# Sheet1.net
KiCad netlist of a schematic drawn in Altium Designer
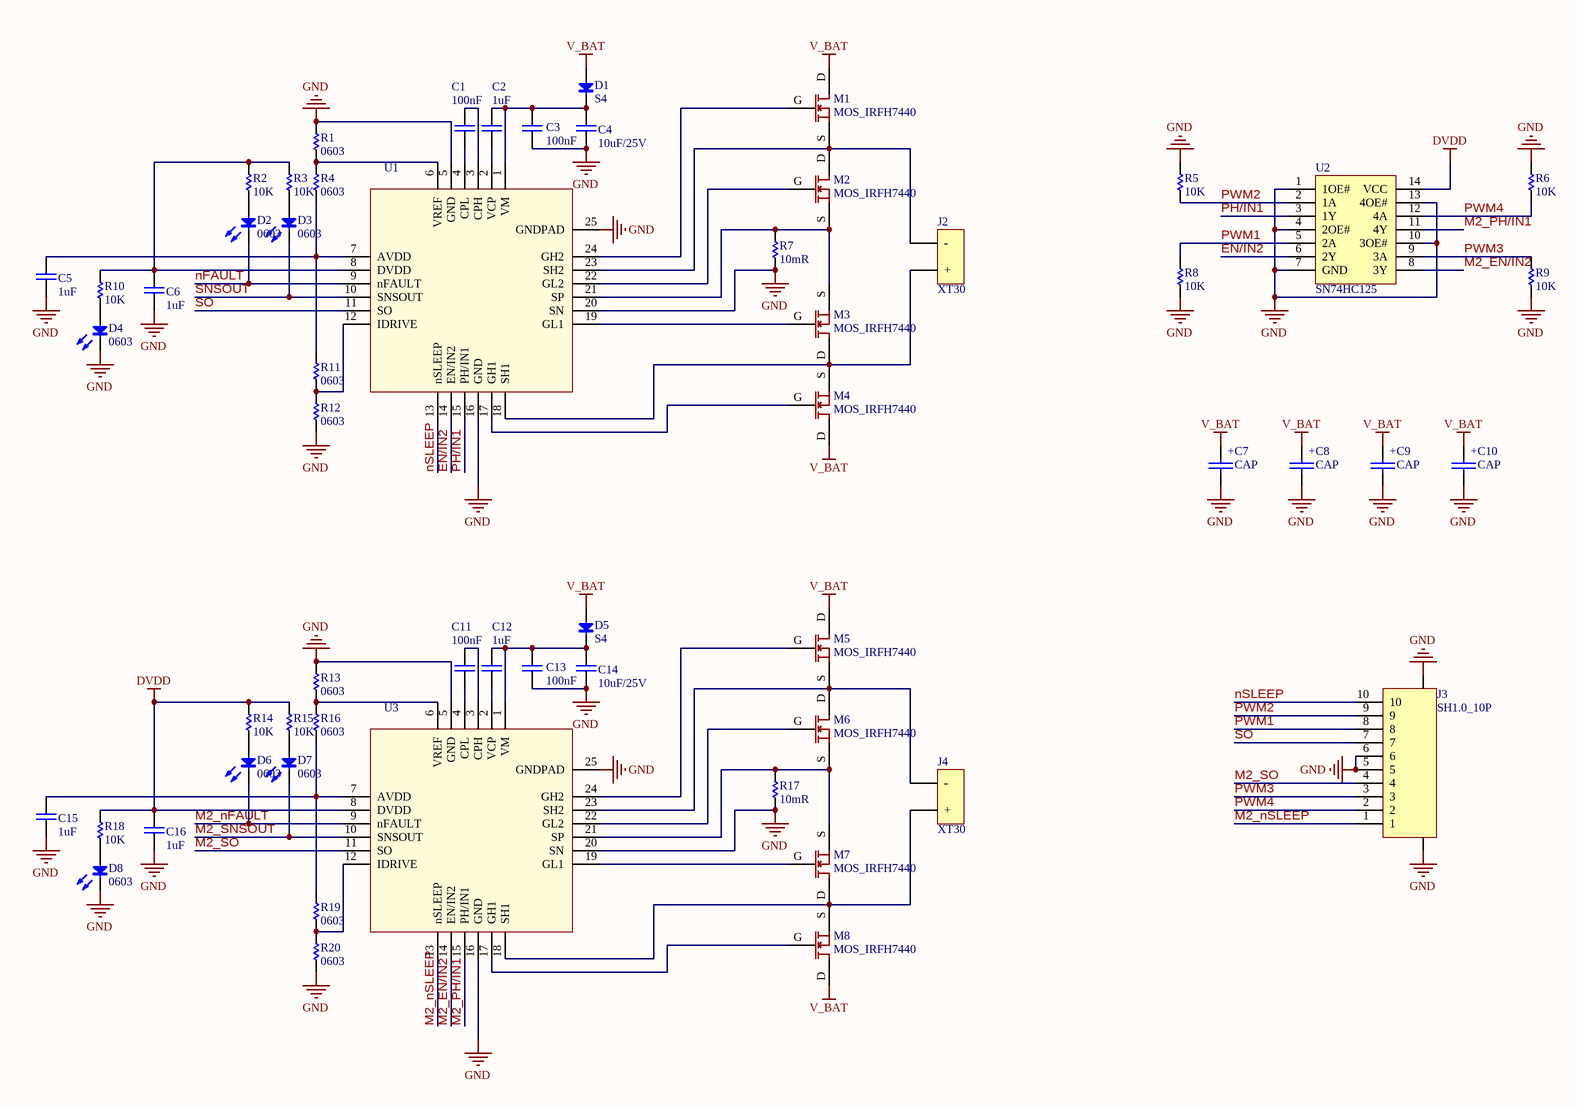
[diagram p0: Sheet1.SchDoc]

(export (version "E")
  (design (tool "Eeschema 10.0.6"))
  (components
    (comp (ref "C1") (value "100nF") (footprint "0603C") (libsource (lib "CPH_LIB") (part "0603-C")))
    (comp (ref "C2") (value "1uF") (footprint "0603C") (libsource (lib "CPH_LIB") (part "0603-C")))
    (comp (ref "C3") (value "100nF") (footprint "0603C") (libsource (lib "CPH_LIB") (part "0603-C")))
    (comp (ref "C4") (value "10uF/25V") (footprint "0805C") (libsource (lib "CPH_LIB") (part "0805-C")))
    (comp (ref "C5") (value "1uF") (footprint "0603C") (libsource (lib "CPH_LIB") (part "0603-C")))
    (comp (ref "C6") (value "1uF") (footprint "0603C") (libsource (lib "CPH_LIB") (part "0603-C")))
    (comp (ref "C7")
      (value "CAP")
      (footprint "CAP-8*11.5")
      (description "插件电解电容")
      (libsource (lib "CPH_LIB") (part "CAP"))
    )
    (comp (ref "C8")
      (value "CAP")
      (footprint "CAP-8*11.5")
      (description "插件电解电容")
      (libsource (lib "CPH_LIB") (part "CAP"))
    )
    (comp (ref "C9")
      (value "CAP")
      (footprint "CAP-8*11.5")
      (description "插件电解电容")
      (libsource (lib "CPH_LIB") (part "CAP"))
    )
    (comp (ref "C10")
      (value "CAP")
      (footprint "CAP-8*11.5")
      (description "插件电解电容")
      (libsource (lib "CPH_LIB") (part "CAP"))
    )
    (comp (ref "C11") (value "100nF") (footprint "0603C") (libsource (lib "CPH_LIB") (part "0603-C")))
    (comp (ref "C12") (value "1uF") (footprint "0603C") (libsource (lib "CPH_LIB") (part "0603-C")))
    (comp (ref "C13") (value "100nF") (footprint "0603C") (libsource (lib "CPH_LIB") (part "0603-C")))
    (comp (ref "C14") (value "10uF/25V") (footprint "0805C") (libsource (lib "CPH_LIB") (part "0805-C")))
    (comp (ref "C15") (value "1uF") (footprint "0603C") (libsource (lib "CPH_LIB") (part "0603-C")))
    (comp (ref "C16") (value "1uF") (footprint "0603C") (libsource (lib "CPH_LIB") (part "0603-C")))
    (comp (ref "D1")
      (value "S4")
      (footprint "SOD-123")
      (description "二极管")
      (libsource (lib "CPH_LIB") (part "DIODE-SOD123"))
    )
    (comp (ref "D2")
      (value "0603")
      (footprint "0603-LED")
      (fields (field (name "DESIGNER") "www.dratk.com"))
      (libsource (lib "CPH_LIB") (part "0603-LED"))
    )
    (comp (ref "D3")
      (value "0603")
      (footprint "0603-LED")
      (fields (field (name "DESIGNER") "www.dratk.com"))
      (libsource (lib "CPH_LIB") (part "0603-LED"))
    )
    (comp (ref "D4")
      (value "0603")
      (footprint "0603-LED")
      (fields (field (name "DESIGNER") "www.dratk.com"))
      (libsource (lib "CPH_LIB") (part "0603-LED"))
    )
    (comp (ref "D5")
      (value "S4")
      (footprint "SOD-123")
      (description "二极管")
      (libsource (lib "CPH_LIB") (part "DIODE-SOD123"))
    )
    (comp (ref "D6")
      (value "0603")
      (footprint "0603-LED")
      (fields (field (name "DESIGNER") "www.dratk.com"))
      (libsource (lib "CPH_LIB") (part "0603-LED"))
    )
    (comp (ref "D7")
      (value "0603")
      (footprint "0603-LED")
      (fields (field (name "DESIGNER") "www.dratk.com"))
      (libsource (lib "CPH_LIB") (part "0603-LED"))
    )
    (comp (ref "D8")
      (value "0603")
      (footprint "0603-LED")
      (fields (field (name "DESIGNER") "www.dratk.com"))
      (libsource (lib "CPH_LIB") (part "0603-LED"))
    )
    (comp (ref "J2")
      (value "XT30")
      (footprint "AMASS_XT30_M")
      (description "XT30_M")
      (libsource (lib "CPH_LIB") (part "AMASS_XT30_M"))
    )
    (comp (ref "J3")
      (value "SH1.0_10P")
      (footprint "SH1.0_10P")
      (libsource (lib "CPH_LIB") (part "SH1.0_10P"))
    )
    (comp (ref "J4")
      (value "XT30")
      (footprint "AMASS_XT30_M")
      (description "XT30_M")
      (libsource (lib "CPH_LIB") (part "AMASS_XT30_M"))
    )
    (comp (ref "M1")
      (value "MOS_IRFH7440")
      (footprint "MOS_IRFH7440")
      (description "NMOS")
      (libsource (lib "CPH_LIB") (part "MOS_IRFH7440"))
    )
    (comp (ref "M2")
      (value "MOS_IRFH7440")
      (footprint "MOS_IRFH7440")
      (description "NMOS")
      (libsource (lib "CPH_LIB") (part "MOS_IRFH7440"))
    )
    (comp (ref "M3")
      (value "MOS_IRFH7440")
      (footprint "MOS_IRFH7440")
      (description "NMOS")
      (libsource (lib "CPH_LIB") (part "MOS_IRFH7440"))
    )
    (comp (ref "M4")
      (value "MOS_IRFH7440")
      (footprint "MOS_IRFH7440")
      (description "NMOS")
      (libsource (lib "CPH_LIB") (part "MOS_IRFH7440"))
    )
    (comp (ref "M5")
      (value "MOS_IRFH7440")
      (footprint "MOS_IRFH7440")
      (description "NMOS")
      (libsource (lib "CPH_LIB") (part "MOS_IRFH7440"))
    )
    (comp (ref "M6")
      (value "MOS_IRFH7440")
      (footprint "MOS_IRFH7440")
      (description "NMOS")
      (libsource (lib "CPH_LIB") (part "MOS_IRFH7440"))
    )
    (comp (ref "M7")
      (value "MOS_IRFH7440")
      (footprint "MOS_IRFH7440")
      (description "NMOS")
      (libsource (lib "CPH_LIB") (part "MOS_IRFH7440"))
    )
    (comp (ref "M8")
      (value "MOS_IRFH7440")
      (footprint "MOS_IRFH7440")
      (description "NMOS")
      (libsource (lib "CPH_LIB") (part "MOS_IRFH7440"))
    )
    (comp (ref "R1") (value "0603") (footprint "0603R") (libsource (lib "CPH_LIB") (part "0603-R")))
    (comp (ref "R2") (value "10K") (footprint "0603R") (libsource (lib "CPH_LIB") (part "0603-R")))
    (comp (ref "R3") (value "10K") (footprint "0603R") (libsource (lib "CPH_LIB") (part "0603-R")))
    (comp (ref "R4") (value "0603") (footprint "0603R") (libsource (lib "CPH_LIB") (part "0603-R")))
    (comp (ref "R5") (value "10K") (footprint "0603R") (libsource (lib "CPH_LIB") (part "0603-R")))
    (comp (ref "R6") (value "10K") (footprint "0603R") (libsource (lib "CPH_LIB") (part "0603-R")))
    (comp (ref "R7") (value "10mR") (footprint "2512R") (libsource (lib "CPH_LIB") (part "2512-R")))
    (comp (ref "R8") (value "10K") (footprint "0603R") (libsource (lib "CPH_LIB") (part "0603-R")))
    (comp (ref "R9") (value "10K") (footprint "0603R") (libsource (lib "CPH_LIB") (part "0603-R")))
    (comp (ref "R10") (value "10K") (footprint "0603R") (libsource (lib "CPH_LIB") (part "0603-R")))
    (comp (ref "R11") (value "0603") (footprint "0603R") (libsource (lib "CPH_LIB") (part "0603-R")))
    (comp (ref "R12") (value "0603") (footprint "0603R") (libsource (lib "CPH_LIB") (part "0603-R")))
    (comp (ref "R13") (value "0603") (footprint "0603R") (libsource (lib "CPH_LIB") (part "0603-R")))
    (comp (ref "R14") (value "10K") (footprint "0603R") (libsource (lib "CPH_LIB") (part "0603-R")))
    (comp (ref "R15") (value "10K") (footprint "0603R") (libsource (lib "CPH_LIB") (part "0603-R")))
    (comp (ref "R16") (value "0603") (footprint "0603R") (libsource (lib "CPH_LIB") (part "0603-R")))
    (comp (ref "R17") (value "10mR") (footprint "2512R") (libsource (lib "CPH_LIB") (part "2512-R")))
    (comp (ref "R18") (value "10K") (footprint "0603R") (libsource (lib "CPH_LIB") (part "0603-R")))
    (comp (ref "R19") (value "0603") (footprint "0603R") (libsource (lib "CPH_LIB") (part "0603-R")))
    (comp (ref "R20") (value "0603") (footprint "0603R") (libsource (lib "CPH_LIB") (part "0603-R")))
    (comp (ref "U1") (value "DRV8701") (footprint "DRV8701") (libsource (lib "CPH_LIB") (part "DRV8701")))
    (comp (ref "U2")
      (value "SN74HC125")
      (footprint "TSSOP-14_L5.0-W4.4-P0.65-LS6.5-BL")
      (description "TI, 2-6V")
      (libsource (lib "CPH_LIB") (part "SN74HC125"))
    )
    (comp (ref "U3") (value "DRV8701") (footprint "DRV8701") (libsource (lib "CPH_LIB") (part "DRV8701")))
  )
  (nets
    (net (code "1") (name "/EN{slash}IN2") (class "Default")
      (node (ref "U1") (pin "14") (pinfunction "EN/IN2_14") (pintype "passive"))
      (node (ref "U2") (pin "6") (pinfunction "2Y_6") (pintype "passive"))
    )
    (net (code "2") (name "/M2_EN{slash}IN2") (class "Default")
      (node (ref "U2") (pin "8") (pinfunction "3Y_8") (pintype "passive"))
      (node (ref "U3") (pin "14") (pinfunction "EN/IN2_14") (pintype "passive"))
    )
    (net (code "3") (name "/M2_PH{slash}IN1") (class "Default")
      (node (ref "U2") (pin "11") (pinfunction "4Y_11") (pintype "passive"))
      (node (ref "U3") (pin "15") (pinfunction "PH/IN1_15") (pintype "passive"))
    )
    (net (code "4") (name "/M2_SNSOUT") (class "Default")
      (node (ref "D7") (pin "2") (pinfunction "2_2") (pintype "passive"))
      (node (ref "U3") (pin "10") (pinfunction "SNSOUT_10") (pintype "passive"))
    )
    (net (code "5") (name "/M2_SO") (class "Default")
      (node (ref "J3") (pin "4") (pinfunction "4_4") (pintype "passive"))
      (node (ref "U3") (pin "11") (pinfunction "SO_11") (pintype "passive"))
    )
    (net (code "6") (name "/M2_nFAULT") (class "Default")
      (node (ref "D6") (pin "2") (pinfunction "2_2") (pintype "passive"))
      (node (ref "U3") (pin "9") (pinfunction "nFAULT_9") (pintype "passive"))
    )
    (net (code "7") (name "/M2_nSLEEP") (class "Default")
      (node (ref "J3") (pin "1") (pinfunction "1_1") (pintype "passive"))
      (node (ref "U3") (pin "13") (pinfunction "nSLEEP_13") (pintype "passive"))
    )
    (net (code "8") (name "/PH{slash}IN1") (class "Default")
      (node (ref "U1") (pin "15") (pinfunction "PH/IN1_15") (pintype "passive"))
      (node (ref "U2") (pin "3") (pinfunction "1Y_3") (pintype "passive"))
    )
    (net (code "9") (name "/PWM1") (class "Default")
      (node (ref "J3") (pin "8") (pinfunction "8_8") (pintype "passive"))
      (node (ref "R8") (pin "1") (pinfunction "1_1") (pintype "passive"))
      (node (ref "U2") (pin "5") (pinfunction "2A_5") (pintype "passive"))
    )
    (net (code "10") (name "/PWM2") (class "Default")
      (node (ref "J3") (pin "9") (pinfunction "9_9") (pintype "passive"))
      (node (ref "R5") (pin "2") (pinfunction "2_2") (pintype "passive"))
      (node (ref "U2") (pin "2") (pinfunction "1A_2") (pintype "passive"))
    )
    (net (code "11") (name "/PWM3") (class "Default")
      (node (ref "J3") (pin "3") (pinfunction "3_3") (pintype "passive"))
      (node (ref "R9") (pin "1") (pinfunction "1_1") (pintype "passive"))
      (node (ref "U2") (pin "9") (pinfunction "3A_9") (pintype "passive"))
    )
    (net (code "12") (name "/PWM4") (class "Default")
      (node (ref "J3") (pin "2") (pinfunction "2_2") (pintype "passive"))
      (node (ref "R6") (pin "1") (pinfunction "1_1") (pintype "passive"))
      (node (ref "U2") (pin "12") (pinfunction "4A_12") (pintype "passive"))
    )
    (net (code "13") (name "/SNSOUT") (class "Default")
      (node (ref "D3") (pin "2") (pinfunction "2_2") (pintype "passive"))
      (node (ref "U1") (pin "10") (pinfunction "SNSOUT_10") (pintype "passive"))
    )
    (net (code "14") (name "/SO") (class "Default")
      (node (ref "J3") (pin "7") (pinfunction "7_7") (pintype "passive"))
      (node (ref "U1") (pin "11") (pinfunction "SO_11") (pintype "passive"))
    )
    (net (code "15") (name "/nFAULT") (class "Default")
      (node (ref "D2") (pin "2") (pinfunction "2_2") (pintype "passive"))
      (node (ref "U1") (pin "9") (pinfunction "nFAULT_9") (pintype "passive"))
    )
    (net (code "16") (name "/nSLEEP") (class "Default")
      (node (ref "J3") (pin "10") (pinfunction "10_10") (pintype "passive"))
      (node (ref "U1") (pin "13") (pinfunction "nSLEEP_13") (pintype "passive"))
    )
    (net (code "17") (name "DVDD") (class "Default")
      (node (ref "C16") (pin "2") (pinfunction "2_2") (pintype "passive"))
      (node (ref "R14") (pin "1") (pinfunction "1_1") (pintype "passive"))
      (node (ref "R15") (pin "1") (pinfunction "1_1") (pintype "passive"))
      (node (ref "R18") (pin "1") (pinfunction "1_1") (pintype "passive"))
      (node (ref "U2") (pin "14") (pinfunction "VCC_14") (pintype "passive"))
      (node (ref "U3") (pin "8") (pinfunction "DVDD_8") (pintype "passive"))
    )
    (net (code "18") (name "GND") (class "Default")
      (node (ref "C10") (pin "2") (pinfunction "2_2") (pintype "passive"))
      (node (ref "C13") (pin "2") (pinfunction "2_2") (pintype "passive"))
      (node (ref "C14") (pin "1") (pinfunction "1_1") (pintype "passive"))
      (node (ref "C15") (pin "2") (pinfunction "2_2") (pintype "passive"))
      (node (ref "C16") (pin "1") (pinfunction "1_1") (pintype "passive"))
      (node (ref "C3") (pin "2") (pinfunction "2_2") (pintype "passive"))
      (node (ref "C4") (pin "1") (pinfunction "1_1") (pintype "passive"))
      (node (ref "C5") (pin "2") (pinfunction "2_2") (pintype "passive"))
      (node (ref "C6") (pin "1") (pinfunction "1_1") (pintype "passive"))
      (node (ref "C7") (pin "2") (pinfunction "2_2") (pintype "passive"))
      (node (ref "C8") (pin "2") (pinfunction "2_2") (pintype "passive"))
      (node (ref "C9") (pin "2") (pinfunction "2_2") (pintype "passive"))
      (node (ref "D4") (pin "2") (pinfunction "2_2") (pintype "passive"))
      (node (ref "D8") (pin "2") (pinfunction "2_2") (pintype "passive"))
      (node (ref "J3") (pin "11") (pinfunction "11_11") (pintype "passive"))
      (node (ref "J3") (pin "12") (pinfunction "12_12") (pintype "passive"))
      (node (ref "J3") (pin "5") (pinfunction "5_5") (pintype "passive"))
      (node (ref "J3") (pin "6") (pinfunction "6_6") (pintype "passive"))
      (node (ref "R1") (pin "2") (pinfunction "2_2") (pintype "passive"))
      (node (ref "R12") (pin "2") (pinfunction "2_2") (pintype "passive"))
      (node (ref "R13") (pin "2") (pinfunction "2_2") (pintype "passive"))
      (node (ref "R17") (pin "2") (pinfunction "2_2") (pintype "passive"))
      (node (ref "R20") (pin "2") (pinfunction "2_2") (pintype "passive"))
      (node (ref "R5") (pin "1") (pinfunction "1_1") (pintype "passive"))
      (node (ref "R6") (pin "2") (pinfunction "2_2") (pintype "passive"))
      (node (ref "R7") (pin "2") (pinfunction "2_2") (pintype "passive"))
      (node (ref "R8") (pin "2") (pinfunction "2_2") (pintype "passive"))
      (node (ref "R9") (pin "2") (pinfunction "2_2") (pintype "passive"))
      (node (ref "U1") (pin "16") (pinfunction "GND_16") (pintype "passive"))
      (node (ref "U1") (pin "20") (pinfunction "SN_20") (pintype "passive"))
      (node (ref "U1") (pin "25") (pinfunction "GNDPAD_25") (pintype "passive"))
      (node (ref "U1") (pin "5") (pinfunction "GND_5") (pintype "passive"))
      (node (ref "U2") (pin "1") (pinfunction "1OE#_1") (pintype "passive"))
      (node (ref "U2") (pin "10") (pinfunction "3OE#_10") (pintype "passive"))
      (node (ref "U2") (pin "13") (pinfunction "4OE#_13") (pintype "passive"))
      (node (ref "U2") (pin "4") (pinfunction "2OE#_4") (pintype "passive"))
      (node (ref "U2") (pin "7") (pinfunction "GND_7") (pintype "passive"))
      (node (ref "U3") (pin "16") (pinfunction "GND_16") (pintype "passive"))
      (node (ref "U3") (pin "20") (pinfunction "SN_20") (pintype "passive"))
      (node (ref "U3") (pin "25") (pinfunction "GNDPAD_25") (pintype "passive"))
      (node (ref "U3") (pin "5") (pinfunction "GND_5") (pintype "passive"))
    )
    (net (code "19") (name "Net-(D2-Pad1)") (class "Default")
      (node (ref "D2") (pin "1") (pinfunction "1_1") (pintype "passive"))
      (node (ref "R2") (pin "2") (pinfunction "2_2") (pintype "passive"))
    )
    (net (code "20") (name "Net-(D3-Pad1)") (class "Default")
      (node (ref "D3") (pin "1") (pinfunction "1_1") (pintype "passive"))
      (node (ref "R3") (pin "2") (pinfunction "2_2") (pintype "passive"))
    )
    (net (code "21") (name "Net-(D4-Pad1)") (class "Default")
      (node (ref "D4") (pin "1") (pinfunction "1_1") (pintype "passive"))
      (node (ref "R10") (pin "2") (pinfunction "2_2") (pintype "passive"))
    )
    (net (code "22") (name "Net-(D6-Pad1)") (class "Default")
      (node (ref "D6") (pin "1") (pinfunction "1_1") (pintype "passive"))
      (node (ref "R14") (pin "2") (pinfunction "2_2") (pintype "passive"))
    )
    (net (code "23") (name "Net-(D7-Pad1)") (class "Default")
      (node (ref "D7") (pin "1") (pinfunction "1_1") (pintype "passive"))
      (node (ref "R15") (pin "2") (pinfunction "2_2") (pintype "passive"))
    )
    (net (code "24") (name "Net-(D8-Pad1)") (class "Default")
      (node (ref "D8") (pin "1") (pinfunction "1_1") (pintype "passive"))
      (node (ref "R18") (pin "2") (pinfunction "2_2") (pintype "passive"))
    )
    (net (code "25") (name "Net-(J2-+)") (class "Default")
      (node (ref "J2") (pin "1") (pinfunction "+_1") (pintype "passive"))
      (node (ref "M3") (pin "D") (pintype "passive"))
      (node (ref "M4") (pin "S") (pintype "passive"))
      (node (ref "U1") (pin "18") (pinfunction "SH1_18") (pintype "passive"))
    )
    (net (code "26") (name "Net-(J2--)") (class "Default")
      (node (ref "J2") (pin "2") (pinfunction "-_2") (pintype "passive"))
      (node (ref "M1") (pin "S") (pintype "passive"))
      (node (ref "M2") (pin "D") (pintype "passive"))
      (node (ref "U1") (pin "23") (pinfunction "SH2_23") (pintype "passive"))
    )
    (net (code "27") (name "Net-(J4-+)") (class "Default")
      (node (ref "J4") (pin "1") (pinfunction "+_1") (pintype "passive"))
      (node (ref "M7") (pin "D") (pintype "passive"))
      (node (ref "M8") (pin "S") (pintype "passive"))
      (node (ref "U3") (pin "18") (pinfunction "SH1_18") (pintype "passive"))
    )
    (net (code "28") (name "Net-(J4--)") (class "Default")
      (node (ref "J4") (pin "2") (pinfunction "-_2") (pintype "passive"))
      (node (ref "M5") (pin "S") (pintype "passive"))
      (node (ref "M6") (pin "D") (pintype "passive"))
      (node (ref "U3") (pin "23") (pinfunction "SH2_23") (pintype "passive"))
    )
    (net (code "29") (name "Net-(U1-AVDD)") (class "Default")
      (node (ref "C5") (pin "1") (pinfunction "1_1") (pintype "passive"))
      (node (ref "R11") (pin "1") (pinfunction "1_1") (pintype "passive"))
      (node (ref "R4") (pin "1") (pinfunction "1_1") (pintype "passive"))
      (node (ref "U1") (pin "7") (pinfunction "AVDD_7") (pintype "passive"))
    )
    (net (code "30") (name "Net-(U1-CPH)") (class "Default")
      (node (ref "C1") (pin "1") (pinfunction "1_1") (pintype "passive"))
      (node (ref "U1") (pin "3") (pinfunction "CPH_3") (pintype "passive"))
    )
    (net (code "31") (name "Net-(U1-CPL)") (class "Default")
      (node (ref "C1") (pin "2") (pinfunction "2_2") (pintype "passive"))
      (node (ref "U1") (pin "4") (pinfunction "CPL_4") (pintype "passive"))
    )
    (net (code "32") (name "Net-(U1-DVDD)") (class "Default")
      (node (ref "C6") (pin "2") (pinfunction "2_2") (pintype "passive"))
      (node (ref "R10") (pin "1") (pinfunction "1_1") (pintype "passive"))
      (node (ref "R2") (pin "1") (pinfunction "1_1") (pintype "passive"))
      (node (ref "R3") (pin "1") (pinfunction "1_1") (pintype "passive"))
      (node (ref "U1") (pin "8") (pinfunction "DVDD_8") (pintype "passive"))
    )
    (net (code "33") (name "Net-(U1-GH1)") (class "Default")
      (node (ref "M4") (pin "G") (pintype "passive"))
      (node (ref "U1") (pin "17") (pinfunction "GH1_17") (pintype "passive"))
    )
    (net (code "34") (name "Net-(U1-GH2)") (class "Default")
      (node (ref "M1") (pin "G") (pintype "passive"))
      (node (ref "U1") (pin "24") (pinfunction "GH2_24") (pintype "passive"))
    )
    (net (code "35") (name "Net-(U1-GL1)") (class "Default")
      (node (ref "M3") (pin "G") (pintype "passive"))
      (node (ref "U1") (pin "19") (pinfunction "GL1_19") (pintype "passive"))
    )
    (net (code "36") (name "Net-(U1-GL2)") (class "Default")
      (node (ref "M2") (pin "G") (pintype "passive"))
      (node (ref "U1") (pin "22") (pinfunction "GL2_22") (pintype "passive"))
    )
    (net (code "37") (name "Net-(U1-IDRIVE)") (class "Default")
      (node (ref "R11") (pin "2") (pinfunction "2_2") (pintype "passive"))
      (node (ref "R12") (pin "1") (pinfunction "1_1") (pintype "passive"))
      (node (ref "U1") (pin "12") (pinfunction "IDRIVE_12") (pintype "passive"))
    )
    (net (code "38") (name "Net-(U1-SP)") (class "Default")
      (node (ref "M2") (pin "S") (pintype "passive"))
      (node (ref "M3") (pin "S") (pintype "passive"))
      (node (ref "R7") (pin "1") (pinfunction "1_1") (pintype "passive"))
      (node (ref "U1") (pin "21") (pinfunction "SP_21") (pintype "passive"))
    )
    (net (code "39") (name "Net-(U1-VCP)") (class "Default")
      (node (ref "C2") (pin "2") (pinfunction "2_2") (pintype "passive"))
      (node (ref "U1") (pin "2") (pinfunction "VCP_2") (pintype "passive"))
    )
    (net (code "40") (name "Net-(U1-VM)") (class "Default")
      (node (ref "C2") (pin "1") (pinfunction "1_1") (pintype "passive"))
      (node (ref "C3") (pin "1") (pinfunction "1_1") (pintype "passive"))
      (node (ref "C4") (pin "2") (pinfunction "2_2") (pintype "passive"))
      (node (ref "D1") (pin "K") (pinfunction "K_K") (pintype "passive"))
      (node (ref "U1") (pin "1") (pinfunction "VM_1") (pintype "passive"))
    )
    (net (code "41") (name "Net-(U1-VREF)") (class "Default")
      (node (ref "R1") (pin "1") (pinfunction "1_1") (pintype "passive"))
      (node (ref "R4") (pin "2") (pinfunction "2_2") (pintype "passive"))
      (node (ref "U1") (pin "6") (pinfunction "VREF_6") (pintype "passive"))
    )
    (net (code "42") (name "Net-(U3-AVDD)") (class "Default")
      (node (ref "C15") (pin "1") (pinfunction "1_1") (pintype "passive"))
      (node (ref "R16") (pin "1") (pinfunction "1_1") (pintype "passive"))
      (node (ref "R19") (pin "1") (pinfunction "1_1") (pintype "passive"))
      (node (ref "U3") (pin "7") (pinfunction "AVDD_7") (pintype "passive"))
    )
    (net (code "43") (name "Net-(U3-CPH)") (class "Default")
      (node (ref "C11") (pin "1") (pinfunction "1_1") (pintype "passive"))
      (node (ref "U3") (pin "3") (pinfunction "CPH_3") (pintype "passive"))
    )
    (net (code "44") (name "Net-(U3-CPL)") (class "Default")
      (node (ref "C11") (pin "2") (pinfunction "2_2") (pintype "passive"))
      (node (ref "U3") (pin "4") (pinfunction "CPL_4") (pintype "passive"))
    )
    (net (code "45") (name "Net-(U3-GH1)") (class "Default")
      (node (ref "M8") (pin "G") (pintype "passive"))
      (node (ref "U3") (pin "17") (pinfunction "GH1_17") (pintype "passive"))
    )
    (net (code "46") (name "Net-(U3-GH2)") (class "Default")
      (node (ref "M5") (pin "G") (pintype "passive"))
      (node (ref "U3") (pin "24") (pinfunction "GH2_24") (pintype "passive"))
    )
    (net (code "47") (name "Net-(U3-GL1)") (class "Default")
      (node (ref "M7") (pin "G") (pintype "passive"))
      (node (ref "U3") (pin "19") (pinfunction "GL1_19") (pintype "passive"))
    )
    (net (code "48") (name "Net-(U3-GL2)") (class "Default")
      (node (ref "M6") (pin "G") (pintype "passive"))
      (node (ref "U3") (pin "22") (pinfunction "GL2_22") (pintype "passive"))
    )
    (net (code "49") (name "Net-(U3-IDRIVE)") (class "Default")
      (node (ref "R19") (pin "2") (pinfunction "2_2") (pintype "passive"))
      (node (ref "R20") (pin "1") (pinfunction "1_1") (pintype "passive"))
      (node (ref "U3") (pin "12") (pinfunction "IDRIVE_12") (pintype "passive"))
    )
    (net (code "50") (name "Net-(U3-SP)") (class "Default")
      (node (ref "M6") (pin "S") (pintype "passive"))
      (node (ref "M7") (pin "S") (pintype "passive"))
      (node (ref "R17") (pin "1") (pinfunction "1_1") (pintype "passive"))
      (node (ref "U3") (pin "21") (pinfunction "SP_21") (pintype "passive"))
    )
    (net (code "51") (name "Net-(U3-VCP)") (class "Default")
      (node (ref "C12") (pin "2") (pinfunction "2_2") (pintype "passive"))
      (node (ref "U3") (pin "2") (pinfunction "VCP_2") (pintype "passive"))
    )
    (net (code "52") (name "Net-(U3-VM)") (class "Default")
      (node (ref "C12") (pin "1") (pinfunction "1_1") (pintype "passive"))
      (node (ref "C13") (pin "1") (pinfunction "1_1") (pintype "passive"))
      (node (ref "C14") (pin "2") (pinfunction "2_2") (pintype "passive"))
      (node (ref "D5") (pin "K") (pinfunction "K_K") (pintype "passive"))
      (node (ref "U3") (pin "1") (pinfunction "VM_1") (pintype "passive"))
    )
    (net (code "53") (name "Net-(U3-VREF)") (class "Default")
      (node (ref "R13") (pin "1") (pinfunction "1_1") (pintype "passive"))
      (node (ref "R16") (pin "2") (pinfunction "2_2") (pintype "passive"))
      (node (ref "U3") (pin "6") (pinfunction "VREF_6") (pintype "passive"))
    )
    (net (code "54") (name "V_BAT") (class "Default")
      (node (ref "C10") (pin "1") (pinfunction "1_1") (pintype "passive"))
      (node (ref "C7") (pin "1") (pinfunction "1_1") (pintype "passive"))
      (node (ref "C8") (pin "1") (pinfunction "1_1") (pintype "passive"))
      (node (ref "C9") (pin "1") (pinfunction "1_1") (pintype "passive"))
      (node (ref "D1") (pin "A") (pinfunction "A_A") (pintype "passive"))
      (node (ref "D5") (pin "A") (pinfunction "A_A") (pintype "passive"))
      (node (ref "M1") (pin "D") (pintype "passive"))
      (node (ref "M4") (pin "D") (pintype "passive"))
      (node (ref "M5") (pin "D") (pintype "passive"))
      (node (ref "M8") (pin "D") (pintype "passive"))
    )
  )
)
